# Dig_Stethoscope.net
KiCad netlist of a schematic drawn in EAGLE
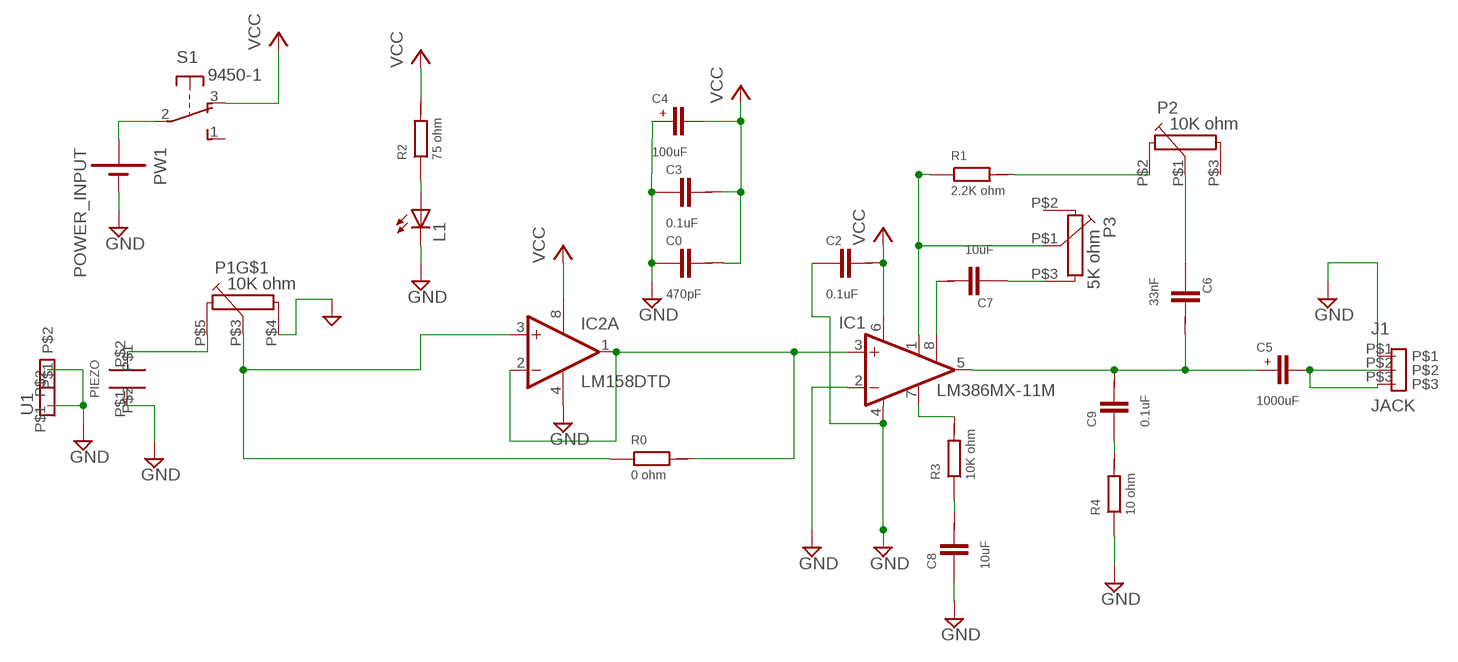
[diagram p0: schematic, sheet 1]

(export (version "E")
  (design (tool "Eeschema 10.0.6"))
  (components
    (comp (ref "C0")
      (value "470pF")
      (footprint "eagle-import:C0603K")
      (libsource (lib "eagle-import") (part "CAP_CERAMIC"))
    )
    (comp (ref "C2")
      (value "0.1uF")
      (footprint "eagle-import:C0603K")
      (libsource (lib "eagle-import") (part "CAP_CERAMIC"))
    )
    (comp (ref "C3")
      (value "0.1uF")
      (footprint "eagle-import:C0603K")
      (libsource (lib "eagle-import") (part "CAP_CERAMIC"))
    )
    (comp (ref "C4")
      (value "100uF")
      (footprint "eagle-import:CAP_100UF")
      (libsource (lib "eagle-import") (part "CAP_100UF"))
    )
    (comp (ref "C5")
      (value "1000uF")
      (footprint "eagle-import:CAP_1000F")
      (libsource (lib "eagle-import") (part "CAP_1000UF"))
    )
    (comp (ref "C6")
      (value "33nF")
      (footprint "eagle-import:C0603K")
      (libsource (lib "eagle-import") (part "CAP_CERAMIC"))
    )
    (comp (ref "C7")
      (value "10uF")
      (footprint "eagle-import:C0603K")
      (libsource (lib "eagle-import") (part "CAP_CERAMIC"))
    )
    (comp (ref "C8")
      (value "10uF")
      (footprint "eagle-import:C0603K")
      (libsource (lib "eagle-import") (part "CAP_CERAMIC"))
    )
    (comp (ref "C9")
      (value "0.1uF")
      (footprint "eagle-import:C0603K")
      (libsource (lib "eagle-import") (part "CAP_CERAMIC"))
    )
    (comp (ref "IC1")
      (value "LM386MX-11M")
      (footprint "eagle-import:SO08")
      (libsource (lib "eagle-import") (part "LM386MX-1M1"))
    )
    (comp (ref "IC2")
      (value "LM158DTD")
      (footprint "eagle-import:SO08")
      (libsource (lib "eagle-import") (part "LM158DTD"))
    )
    (comp (ref "J1")
      (value "JACK")
      (footprint "eagle-import:JACK")
      (libsource (lib "eagle-import") (part "JACK"))
    )
    (comp (ref "L1")
      (value "L140_LED")
      (footprint "eagle-import:LTW_LED")
      (libsource (lib "eagle-import") (part "L140_LED"))
    )
    (comp (ref "P1")
      (value "10K ohm")
      (footprint "eagle-import:DIP_POT")
      (libsource (lib "eagle-import") (part "POT_DIP_REAR_MOUNT"))
    )
    (comp (ref "P2")
      (value "10K ohm")
      (footprint "eagle-import:TC33X-1_2")
      (libsource (lib "eagle-import") (part "TC33X-1/2"))
    )
    (comp (ref "P3")
      (value "5K ohm")
      (footprint "eagle-import:TC33X-1_2")
      (libsource (lib "eagle-import") (part "TC33X-1/2"))
    )
    (comp (ref "PIEZO")
      (value "PIEZO_INPUT")
      (footprint "eagle-import:2_PIEZO_DIP")
      (libsource (lib "eagle-import") (part "PIEZO_INPUT"))
    )
    (comp (ref "PW1")
      (value "POWER_INPUT")
      (footprint "eagle-import:2_POWER_DIP")
      (libsource (lib "eagle-import") (part "POWER_INPUT"))
    )
    (comp (ref "R0")
      (value "0 ohm")
      (footprint "eagle-import:C1206K")
      (libsource (lib "eagle-import") (part "RESISTOR"))
    )
    (comp (ref "R1")
      (value "2.2K ohm")
      (footprint "eagle-import:C1206K")
      (libsource (lib "eagle-import") (part "RESISTOR"))
    )
    (comp (ref "R2")
      (value "75 ohm")
      (footprint "eagle-import:C1206K")
      (libsource (lib "eagle-import") (part "RESISTOR"))
    )
    (comp (ref "R3")
      (value "10K ohm")
      (footprint "eagle-import:C1206K")
      (libsource (lib "eagle-import") (part "RESISTOR"))
    )
    (comp (ref "R4")
      (value "10 ohm")
      (footprint "eagle-import:C1206K")
      (libsource (lib "eagle-import") (part "RESISTOR"))
    )
    (comp (ref "S1")
      (value "9450-1")
      (footprint "eagle-import:9450-1")
      (libsource (lib "eagle-import") (part "9450-1"))
    )
    (comp (ref "U1")
      (value "CLAMP")
      (footprint "eagle-import:CLAMP")
      (libsource (lib "eagle-import") (part "CLAMP"))
    )
  )
  (nets
    (net (code "1") (name "GND") (class "Default")
      (node (ref "C0") (pin "1") (pinfunction "P$1_1") (pintype "bidirectional"))
      (node (ref "C2") (pin "1") (pinfunction "P$1_1") (pintype "bidirectional"))
      (node (ref "C3") (pin "1") (pinfunction "P$1_1") (pintype "bidirectional"))
      (node (ref "C4") (pin "P$2") (pinfunction "1_P$2") (pintype "bidirectional"))
      (node (ref "C8") (pin "1") (pinfunction "P$1_1") (pintype "bidirectional"))
      (node (ref "IC1") (pin "2") (pinfunction "-IN_2") (pintype "input"))
      (node (ref "IC1") (pin "4") (pinfunction "GND_4") (pintype "power_in"))
      (node (ref "IC2") (pin "4") (pinfunction "V-_4") (pintype "power_in"))
      (node (ref "J1") (pin "P$1") (pinfunction "P$1_P$1") (pintype "bidirectional"))
      (node (ref "L1") (pin "CATH_2") (pinfunction "C_CATH_2") (pintype "passive"))
      (node (ref "P1") (pin "P$1") (pinfunction "GND_P$1") (pintype "power_in"))
      (node (ref "P1") (pin "P$2") (pinfunction "GND_P$2") (pintype "power_in"))
      (node (ref "P1") (pin "P$4") (pinfunction "1E_P$4") (pintype "passive"))
      (node (ref "PIEZO") (pin "P$1") (pinfunction "P$1_P$1") (pintype "bidirectional"))
      (node (ref "PW1") (pin "P$2") (pinfunction "-_P$2") (pintype "power_in"))
      (node (ref "R4") (pin "1") (pinfunction "1_1") (pintype "bidirectional"))
      (node (ref "U1") (pin "P$1") (pinfunction "P$1_P$1") (pintype "bidirectional"))
      (node (ref "U1") (pin "P$2") (pinfunction "P$2_P$2") (pintype "bidirectional"))
    )
    (net (code "2") (name "Net-(C5-1)") (class "Default")
      (node (ref "C5") (pin "P$2") (pinfunction "1_P$2") (pintype "bidirectional"))
      (node (ref "C6") (pin "2") (pinfunction "P$2_2") (pintype "bidirectional"))
      (node (ref "C9") (pin "2") (pinfunction "P$2_2") (pintype "bidirectional"))
      (node (ref "IC1") (pin "5") (pinfunction "OUT_5") (pintype "output"))
    )
    (net (code "3") (name "Net-(C5-2)") (class "Default")
      (node (ref "C5") (pin "P$1") (pinfunction "2_P$1") (pintype "bidirectional"))
      (node (ref "J1") (pin "P$2") (pinfunction "P$2_P$2") (pintype "bidirectional"))
      (node (ref "J1") (pin "P$3") (pinfunction "P$3_P$3") (pintype "bidirectional"))
    )
    (net (code "4") (name "Net-(C6-P$1)") (class "Default")
      (node (ref "C6") (pin "1") (pinfunction "P$1_1") (pintype "bidirectional"))
      (node (ref "P2") (pin "P$1") (pinfunction "1S_P$1") (pintype "passive"))
    )
    (net (code "5") (name "Net-(C7-P$1)") (class "Default")
      (node (ref "C7") (pin "1") (pinfunction "P$1_1") (pintype "bidirectional"))
      (node (ref "P3") (pin "P$3") (pinfunction "1E_P$3") (pintype "passive"))
    )
    (net (code "6") (name "Net-(C7-P$2)") (class "Default")
      (node (ref "C7") (pin "2") (pinfunction "P$2_2") (pintype "bidirectional"))
      (node (ref "IC1") (pin "8") (pinfunction "GAIN_8") (pintype "passive"))
    )
    (net (code "7") (name "Net-(C8-P$2)") (class "Default")
      (node (ref "C8") (pin "2") (pinfunction "P$2_2") (pintype "bidirectional"))
      (node (ref "R3") (pin "1") (pinfunction "1_1") (pintype "bidirectional"))
    )
    (net (code "8") (name "Net-(C9-P$1)") (class "Default")
      (node (ref "C9") (pin "1") (pinfunction "P$1_1") (pintype "bidirectional"))
      (node (ref "R4") (pin "2") (pinfunction "2_2") (pintype "bidirectional"))
    )
    (net (code "9") (name "Net-(IC1-+IN)") (class "Default")
      (node (ref "IC1") (pin "3") (pinfunction "+IN_3") (pintype "input"))
      (node (ref "IC2") (pin "1") (pinfunction "OUT_1") (pintype "output"))
      (node (ref "IC2") (pin "2") (pinfunction "-IN_2") (pintype "input"))
      (node (ref "R0") (pin "2") (pinfunction "2_2") (pintype "bidirectional"))
    )
    (net (code "10") (name "Net-(IC1-BYPASS)") (class "Default")
      (node (ref "IC1") (pin "7") (pinfunction "BYPASS_7") (pintype "passive"))
      (node (ref "R3") (pin "2") (pinfunction "2_2") (pintype "bidirectional"))
    )
    (net (code "11") (name "Net-(IC2A-+IN)") (class "Default")
      (node (ref "IC2") (pin "3") (pinfunction "+IN_3") (pintype "input"))
      (node (ref "P1") (pin "P$3") (pinfunction "1S_P$3") (pintype "passive"))
      (node (ref "R0") (pin "1") (pinfunction "1_1") (pintype "bidirectional"))
    )
    (net (code "12") (name "Net-(L1-A)") (class "Default")
      (node (ref "L1") (pin "ANODE_1") (pinfunction "A_ANODE_1") (pintype "passive"))
      (node (ref "R2") (pin "1") (pinfunction "1_1") (pintype "bidirectional"))
    )
    (net (code "13") (name "Net-(P1A-1A)") (class "Default")
      (node (ref "P1") (pin "P$5") (pinfunction "1A_P$5") (pintype "passive"))
      (node (ref "PIEZO") (pin "P$2") (pinfunction "P$2_P$2") (pintype "bidirectional"))
    )
    (net (code "14") (name "Net-(P2-1A)") (class "Default")
      (node (ref "P2") (pin "P$2") (pinfunction "1A_P$2") (pintype "passive"))
      (node (ref "R1") (pin "2") (pinfunction "2_2") (pintype "bidirectional"))
    )
    (net (code "15") (name "Net-(P3-1S)") (class "Default")
      (node (ref "IC1") (pin "1") (pinfunction "GAIN_1") (pintype "passive"))
      (node (ref "P3") (pin "P$1") (pinfunction "1S_P$1") (pintype "passive"))
      (node (ref "R1") (pin "1") (pinfunction "1_1") (pintype "bidirectional"))
    )
    (net (code "16") (name "Net-(PW1-+)") (class "Default")
      (node (ref "PW1") (pin "P$1") (pinfunction "+_P$1") (pintype "power_in"))
      (node (ref "S1") (pin "2") (pinfunction "P_2") (pintype "passive"))
    )
    (net (code "17") (name "VCC") (class "Default")
      (node (ref "C0") (pin "2") (pinfunction "P$2_2") (pintype "bidirectional"))
      (node (ref "C2") (pin "2") (pinfunction "P$2_2") (pintype "bidirectional"))
      (node (ref "C3") (pin "2") (pinfunction "P$2_2") (pintype "bidirectional"))
      (node (ref "C4") (pin "P$1") (pinfunction "2_P$1") (pintype "bidirectional"))
      (node (ref "IC1") (pin "6") (pinfunction "VS_6") (pintype "power_in"))
      (node (ref "IC2") (pin "8") (pinfunction "V+_8") (pintype "power_in"))
      (node (ref "R2") (pin "2") (pinfunction "2_2") (pintype "bidirectional"))
      (node (ref "S1") (pin "3") (pinfunction "O_3") (pintype "passive"))
    )
    (net (code "18") (name "unconnected-(P2-1E-PadP$3)") (class "Default")
      (node (ref "P2") (pin "P$3") (pinfunction "1E_P$3") (pintype "passive"))
    )
    (net (code "19") (name "unconnected-(P3-1A-PadP$2)") (class "Default")
      (node (ref "P3") (pin "P$2") (pinfunction "1A_P$2") (pintype "passive"))
    )
    (net (code "20") (name "unconnected-(S1-S-Pad1)") (class "Default")
      (node (ref "S1") (pin "1") (pinfunction "S_1") (pintype "passive"))
    )
  )
)
